# ETH-W5500.net
KiCad netlist of a schematic drawn in Altium Designer
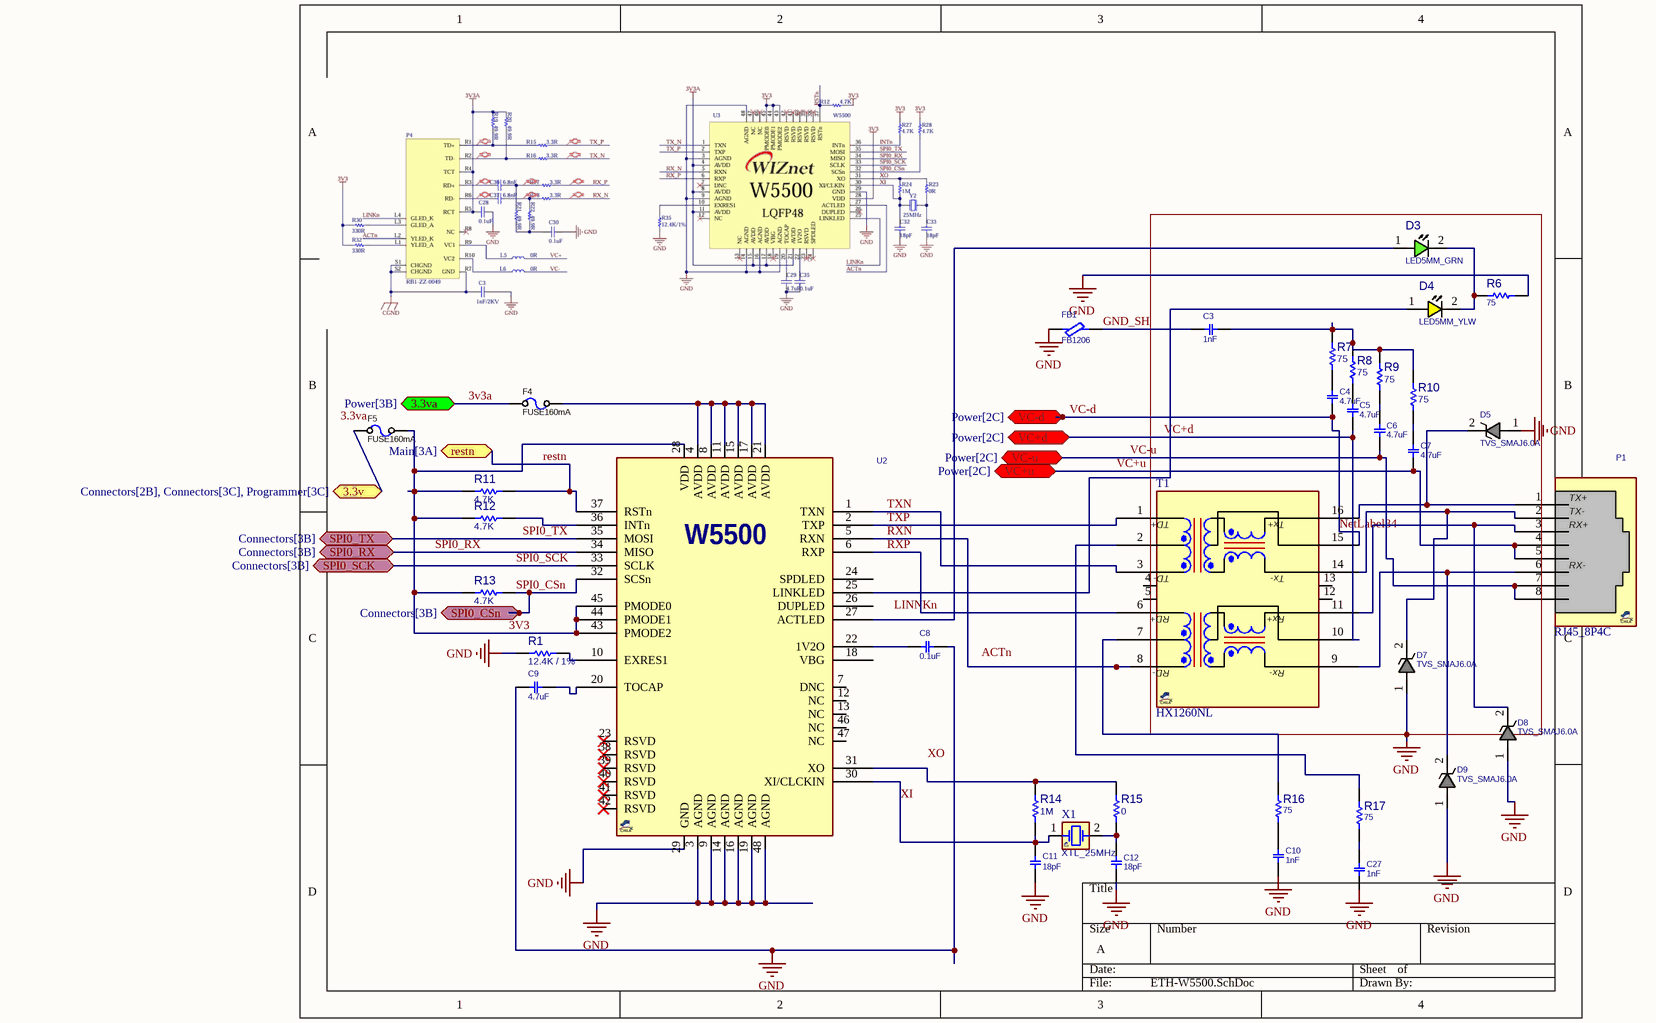
[diagram p0: ETH-W5500.SchDoc]

(export (version "E")
  (design (tool "Eeschema 10.0.6"))
  (components
    (comp (ref "C3")
      (value "1nF")
      (footprint "C_CERM_D3")
      (description "CAP, THD, CER MULTI LAYER,")
      (fields (field (name "MANF_P#") "MANF_PART#") (field (name "MANF") "MANF"))
      (libsource (lib "passive_thd") (part "CAP_THD_CER"))
    )
    (comp (ref "C4")
      (value "4.7uF")
      (footprint "C_CERM_D3")
      (description "CAP, THD, CER MULTI LAYER,")
      (fields (field (name "MANF_P#") "MANF_PART#") (field (name "MANF") "MANF"))
      (libsource (lib "passive_thd") (part "CAP_THD_CER"))
    )
    (comp (ref "C5")
      (value "4.7uF")
      (footprint "C_CERM_D3")
      (description "CAP, THD, CER MULTI LAYER,")
      (fields (field (name "MANF_P#") "MANF_PART#") (field (name "MANF") "MANF"))
      (libsource (lib "passive_thd") (part "CAP_THD_CER"))
    )
    (comp (ref "C6")
      (value "4.7uF")
      (footprint "C_CERM_D3")
      (description "CAP, THD, CER MULTI LAYER,")
      (fields (field (name "MANF_P#") "MANF_PART#") (field (name "MANF") "MANF"))
      (libsource (lib "passive_thd") (part "CAP_THD_CER"))
    )
    (comp (ref "C7")
      (value "4.7uF")
      (footprint "C_CERM_D3")
      (description "CAP, THD, CER MULTI LAYER,")
      (fields (field (name "MANF_P#") "MANF_PART#") (field (name "MANF") "MANF"))
      (libsource (lib "passive_thd") (part "CAP_THD_CER"))
    )
    (comp (ref "C8")
      (value "0.1uF")
      (footprint "C_CERM_D3")
      (description "CAP, THD, CER MULTI LAYER,")
      (fields (field (name "MANF_P#") "MANF_PART#") (field (name "MANF") "MANF"))
      (libsource (lib "passive_thd") (part "CAP_THD_CER"))
    )
    (comp (ref "C9")
      (value "4.7uF")
      (footprint "C_CERM_D3")
      (description "CAP, THD, CER MULTI LAYER,")
      (fields (field (name "MANF_P#") "MANF_PART#") (field (name "MANF") "MANF"))
      (libsource (lib "passive_thd") (part "CAP_THD_CER"))
    )
    (comp (ref "C10")
      (value "1nF")
      (footprint "C_CERM_D3")
      (description "CAP, THD, CER MULTI LAYER,")
      (fields (field (name "MANF_P#") "MANF_PART#") (field (name "MANF") "MANF"))
      (libsource (lib "passive_thd") (part "CAP_THD_CER"))
    )
    (comp (ref "C11")
      (value "18pF")
      (footprint "C_CERM_D3")
      (description "CAP, THD, CER MULTI LAYER,")
      (fields (field (name "MANF_P#") "MANF_PART#") (field (name "MANF") "MANF"))
      (libsource (lib "passive_thd") (part "CAP_THD_CER"))
    )
    (comp (ref "C12")
      (value "18pF")
      (footprint "C_CERM_D3")
      (description "CAP, THD, CER MULTI LAYER,")
      (fields (field (name "MANF_P#") "MANF_PART#") (field (name "MANF") "MANF"))
      (libsource (lib "passive_thd") (part "CAP_THD_CER"))
    )
    (comp (ref "C27")
      (value "1nF")
      (footprint "C_CERM_D3")
      (description "CAP, THD, CER MULTI LAYER,")
      (fields (field (name "MANF_P#") "MANF_PART#") (field (name "MANF") "MANF"))
      (libsource (lib "passive_thd") (part "CAP_THD_CER"))
    )
    (comp (ref "D3")
      (value "LED5MM_GRN")
      (footprint "LED5MM_GRN")
      (description "LED, THD, 5MM, GREEN")
      (fields (field (name "MANF") "MANF") (field (name "MANF_P#") "MANF_PART#"))
      (libsource (lib "led(diode)") (part "LED_THD_5MM_GRN"))
    )
    (comp (ref "D4")
      (value "LED5MM_YLW")
      (footprint "LED5MM_YLW")
      (description "LED, THD, 5MM, YELLOW")
      (fields (field (name "MANF") "MANF") (field (name "MANF_P#") "MANF_PART#"))
      (libsource (lib "led(diode)") (part "LED_THD_5MM_YLW"))
    )
    (comp (ref "D5")
      (value "TVS_SMAJ6.0A")
      (footprint "D_SMA")
      (description "TVS, ESD PROTECT")
      (fields (field (name "MANF_P#") "SMAJ6.0A"))
      (libsource (lib "protect_tvs_esd_fuse") (part "TVS_SMAJ6.0A"))
    )
    (comp (ref "D7")
      (value "TVS_SMAJ6.0A")
      (footprint "D_SMA")
      (description "TVS, ESD PROTECT")
      (fields (field (name "MANF_P#") "SMAJ6.0A"))
      (libsource (lib "protect_tvs_esd_fuse") (part "TVS_SMAJ6.0A"))
    )
    (comp (ref "D8")
      (value "TVS_SMAJ6.0A")
      (footprint "D_SMA")
      (description "TVS, ESD PROTECT")
      (fields (field (name "MANF_P#") "SMAJ6.0A"))
      (libsource (lib "protect_tvs_esd_fuse") (part "TVS_SMAJ6.0A"))
    )
    (comp (ref "D9")
      (value "TVS_SMAJ6.0A")
      (footprint "D_SMA")
      (description "TVS, ESD PROTECT")
      (fields (field (name "MANF_P#") "SMAJ6.0A"))
      (libsource (lib "protect_tvs_esd_fuse") (part "TVS_SMAJ6.0A"))
    )
    (comp (ref "F4")
      (value "FUSE160mA")
      (footprint "F1206")
      (description "Fuse, 160mA, 63VDC, 1206, SMD, Fast Acting")
      (fields (field (name "MANF") "Holly Fuse") (field (name "MANF_P#") "12T-0160L"))
      (libsource (lib "protect_tvs_esd_fuse") (part "FUSE_160mA_1206"))
    )
    (comp (ref "F5")
      (value "FUSE160mA")
      (footprint "F1206")
      (description "Fuse, 160mA, 63VDC, 1206, SMD, Fast Acting")
      (fields (field (name "MANF") "Holly Fuse") (field (name "MANF_P#") "12T-0160L"))
      (libsource (lib "protect_tvs_esd_fuse") (part "FUSE_160mA_1206"))
    )
    (comp (ref "FB1")
      (value "FB1206")
      (footprint "L1206")
      (description "FERRITE_Bead, 1206, 1.5A, 80mOhm, 600@100MHz")
      (fields (field (name "MANF") "Murata") (field (name "MANF_P#") "BLM31PG601SN1L"))
      (libsource (lib "emi_filter") (part "FBEAD_SMD_BLM31PG601"))
    )
    (comp (ref "P1")
      (value "RJ45_8P4C")
      (footprint "RJ45_8_RA_TD")
      (description "RJ45, 8P4C, RightAngle, Tab Down")
      (fields (field (name "MANF") "WURTH") (field (name "MANF_P#") "615008137121, 615008143721"))
      (libsource (lib "conn_rj_ModularJack") (part "RJ45_8P4C_RATD"))
    )
    (comp (ref "R1")
      (value "12.4K / 1%")
      (footprint "R0603")
      (description "RESISTOR, SMD")
      (libsource (lib "passive_smd") (part "RES_SMD"))
    )
    (comp (ref "R6")
      (value "75")
      (footprint "R025W_AX04")
      (description "RESISTOR, THD")
      (fields (field (name "MANF_P#") "RK73H1ETTP4701F") (field (name "MANF") "KOA SPEER"))
      (libsource (lib "passive_thd") (part "RES_THD"))
    )
    (comp (ref "R7")
      (value "75")
      (footprint "R0402")
      (description "RESISTOR, SMD")
      (libsource (lib "passive_smd") (part "RES_SMD"))
    )
    (comp (ref "R8")
      (value "75")
      (footprint "R0402")
      (description "RESISTOR, SMD")
      (libsource (lib "passive_smd") (part "RES_SMD"))
    )
    (comp (ref "R9")
      (value "75")
      (footprint "R0402")
      (description "RESISTOR, SMD")
      (libsource (lib "passive_smd") (part "RES_SMD"))
    )
    (comp (ref "R10")
      (value "75")
      (footprint "R0402")
      (description "RESISTOR, SMD")
      (libsource (lib "passive_smd") (part "RES_SMD"))
    )
    (comp (ref "R11")
      (value "4.7K")
      (footprint "R1206")
      (description "RESISTOR, SMD")
      (libsource (lib "passive_smd") (part "RES_SMD_1206"))
    )
    (comp (ref "R12")
      (value "4.7K")
      (footprint "R1206")
      (description "RESISTOR, SMD")
      (libsource (lib "passive_smd") (part "RES_SMD_1206"))
    )
    (comp (ref "R13")
      (value "4.7K")
      (footprint "R1206")
      (description "RESISTOR, SMD")
      (libsource (lib "passive_smd") (part "RES_SMD_1206"))
    )
    (comp (ref "R14")
      (value "1M")
      (footprint "R0603")
      (description "RESISTOR, SMD")
      (libsource (lib "passive_smd") (part "RES_SMD_0603"))
    )
    (comp (ref "R15")
      (value "0")
      (footprint "R0603")
      (description "RESISTOR, SMD")
      (libsource (lib "passive_smd") (part "RES_SMD_0603"))
    )
    (comp (ref "R16")
      (value "75")
      (footprint "R025W_AX04")
      (description "RESISTOR, THD")
      (fields (field (name "MANF_P#") "RK73H1ETTP4701F") (field (name "MANF") "KOA SPEER"))
      (libsource (lib "passive_thd") (part "RES_THD"))
    )
    (comp (ref "R17")
      (value "75")
      (footprint "R025W_AX04")
      (description "RESISTOR, THD")
      (fields (field (name "MANF_P#") "RK73H1ETTP4701F") (field (name "MANF") "KOA SPEER"))
      (libsource (lib "passive_thd") (part "RES_THD"))
    )
    (comp (ref "T1")
      (value "HX1260NL")
      (footprint "SO_16_7W6H")
      (description "Transformer, LAN, 100 Base-T , 1CT:1CT, 350uH")
      (fields (field (name "MANF") "Pulse"))
      (libsource (lib "transformer_ethernet") (part "HX1260NL_SO16"))
    )
    (comp (ref "U2")
      (value "~")
      (footprint "QFG50_48")
      (description "Ethernet Controller, 10/100, SPI, DMA")
      (fields (field (name "MANF") "WIZNET") (field (name "MANF_P#") "W5500"))
      (libsource (lib "ethernet") (part "W5500_QFP48"))
    )
    (comp (ref "X1")
      (value "XTL_25MHz")
      (footprint "XTL_2_5032")
      (description "Crystal 2 5X3.2mm")
      (fields (field (name "MANF") "ABRACON") (field (name "MANF_P#") "ABM3-25.000MHZ-B2-T"))
      (libsource (lib "crystal") (part "XTL_2_25MHz"))
    )
  )
  (nets
    (net (code "1") (name "/3.3v") (class "Default")
      (node (ref "F5") (pin "1") (pinfunction "1_1") (pintype "passive"))
    )
    (net (code "2") (name "/3.3va") (class "Default")
      (node (ref "F4") (pin "1") (pinfunction "1_1") (pintype "passive"))
    )
    (net (code "3") (name "/3V3") (class "Default")
      (node (ref "F5") (pin "2") (pinfunction "2_2") (pintype "passive"))
      (node (ref "R11") (pin "1") (pinfunction "1_1") (pintype "passive"))
      (node (ref "R12") (pin "1") (pinfunction "1_1") (pintype "passive"))
      (node (ref "R13") (pin "1") (pinfunction "1_1") (pintype "passive"))
      (node (ref "U2") (pin "28") (pinfunction "VDD_28") (pintype "passive"))
      (node (ref "U2") (pin "43") (pinfunction "PMODE2_43") (pintype "passive"))
      (node (ref "U2") (pin "44") (pinfunction "PMODE1_44") (pintype "passive"))
      (node (ref "U2") (pin "45") (pinfunction "PMODE0_45") (pintype "passive"))
    )
    (net (code "5") (name "/GND_SH") (class "Default")
      (node (ref "C3") (pin "2") (pinfunction "2_2") (pintype "passive"))
      (node (ref "FB1") (pin "2") (pinfunction "2_2") (pintype "passive"))
    )
    (net (code "7") (name "/NetLabel34") (class "Default")
      (node (ref "C4") (pin "1") (pinfunction "1_1") (pintype "passive"))
      (node (ref "T1") (pin "15") (pinfunction "CTX_15") (pintype "passive"))
    )
    (net (code "8") (name "/RXN") (class "Default")
      (node (ref "T1") (pin "8") (pinfunction "RD-_8") (pintype "passive"))
      (node (ref "U2") (pin "5") (pinfunction "RXN_5") (pintype "passive"))
    )
    (net (code "9") (name "/RXP") (class "Default")
      (node (ref "T1") (pin "6") (pinfunction "RD+_6") (pintype "passive"))
      (node (ref "U2") (pin "6") (pinfunction "RXP_6") (pintype "passive"))
    )
    (net (code "10") (name "/SPI0_CSn") (class "Default")
      (node (ref "R13") (pin "2") (pinfunction "2_2") (pintype "passive"))
      (node (ref "U2") (pin "32") (pinfunction "SCSn_32") (pintype "passive"))
    )
    (net (code "11") (name "/SPI0_RX") (class "Default")
      (node (ref "U2") (pin "34") (pinfunction "MISO_34") (pintype "passive"))
    )
    (net (code "12") (name "/SPI0_SCK") (class "Default")
      (node (ref "U2") (pin "33") (pinfunction "SCLK_33") (pintype "passive"))
    )
    (net (code "13") (name "/SPI0_TX") (class "Default")
      (node (ref "U2") (pin "35") (pinfunction "MOSI_35") (pintype "passive"))
    )
    (net (code "14") (name "/TXN") (class "Default")
      (node (ref "T1") (pin "3") (pinfunction "TD-_3") (pintype "passive"))
      (node (ref "U2") (pin "1") (pinfunction "TXN_1") (pintype "passive"))
    )
    (net (code "15") (name "/TXP") (class "Default")
      (node (ref "T1") (pin "1") (pinfunction "TD+_1") (pintype "passive"))
      (node (ref "U2") (pin "2") (pinfunction "TXP_2") (pintype "passive"))
    )
    (net (code "16") (name "/VC+d") (class "Default")
      (node (ref "C5") (pin "1") (pinfunction "1_1") (pintype "passive"))
      (node (ref "T1") (pin "10") (pinfunction "CRX_10") (pintype "passive"))
    )
    (net (code "17") (name "/VC+u") (class "Default")
      (node (ref "C7") (pin "1") (pinfunction "1_1") (pintype "passive"))
      (node (ref "P1") (pin "4") (pinfunction "NC_4") (pintype "passive"))
      (node (ref "P1") (pin "5") (pinfunction "NC_5") (pintype "passive"))
    )
    (net (code "18") (name "/VC-u") (class "Default")
      (node (ref "C6") (pin "1") (pinfunction "1_1") (pintype "passive"))
      (node (ref "P1") (pin "7") (pinfunction "NC_7") (pintype "passive"))
      (node (ref "P1") (pin "8") (pinfunction "NC_8") (pintype "passive"))
    )
    (net (code "19") (name "/XI") (class "Default")
      (node (ref "C11") (pin "2") (pinfunction "2_2") (pintype "passive"))
      (node (ref "R14") (pin "1") (pinfunction "1_1") (pintype "passive"))
      (node (ref "U2") (pin "30") (pinfunction "XI/CLCKIN_30") (pintype "passive"))
      (node (ref "X1") (pin "1") (pinfunction "OSC1_1") (pintype "passive"))
    )
    (net (code "21") (name "/restn") (class "Default")
      (node (ref "R11") (pin "2") (pinfunction "2_2") (pintype "passive"))
      (node (ref "U2") (pin "37") (pinfunction "RSTn_37") (pintype "passive"))
    )
    (net (code "22") (name "GND") (class "Default")
      (node (ref "C10") (pin "1") (pinfunction "1_1") (pintype "passive"))
      (node (ref "C11") (pin "1") (pinfunction "1_1") (pintype "passive"))
      (node (ref "C12") (pin "1") (pinfunction "1_1") (pintype "passive"))
      (node (ref "C27") (pin "1") (pinfunction "1_1") (pintype "passive"))
      (node (ref "C8") (pin "2") (pinfunction "2_2") (pintype "passive"))
      (node (ref "C9") (pin "1") (pinfunction "1_1") (pintype "passive"))
      (node (ref "D5") (pin "1") (pinfunction "1_1") (pintype "passive"))
      (node (ref "D7") (pin "1") (pinfunction "1_1") (pintype "passive"))
      (node (ref "D8") (pin "1") (pinfunction "1_1") (pintype "passive"))
      (node (ref "D9") (pin "1") (pinfunction "1_1") (pintype "passive"))
      (node (ref "FB1") (pin "1") (pinfunction "1_1") (pintype "passive"))
      (node (ref "R1") (pin "1") (pinfunction "1_1") (pintype "passive"))
      (node (ref "R6") (pin "2") (pinfunction "2_2") (pintype "passive"))
      (node (ref "U2") (pin "14") (pinfunction "AGND_14") (pintype "passive"))
      (node (ref "U2") (pin "16") (pinfunction "AGND_16") (pintype "passive"))
      (node (ref "U2") (pin "19") (pinfunction "AGND_19") (pintype "passive"))
      (node (ref "U2") (pin "29") (pinfunction "GND_29") (pintype "passive"))
      (node (ref "U2") (pin "3") (pinfunction "AGND_3") (pintype "passive"))
      (node (ref "U2") (pin "48") (pinfunction "AGND_48") (pintype "passive"))
      (node (ref "U2") (pin "9") (pinfunction "AGND_9") (pintype "passive"))
    )
    (net (code "23") (name "Net-(C3-Pad1)") (class "Default")
      (node (ref "C3") (pin "1") (pinfunction "1_1") (pintype "passive"))
      (node (ref "R10") (pin "2") (pinfunction "2_2") (pintype "passive"))
      (node (ref "R7") (pin "2") (pinfunction "2_2") (pintype "passive"))
      (node (ref "R8") (pin "2") (pinfunction "2_2") (pintype "passive"))
      (node (ref "R9") (pin "2") (pinfunction "2_2") (pintype "passive"))
    )
    (net (code "24") (name "Net-(C4-Pad2)") (class "Default")
      (node (ref "C4") (pin "2") (pinfunction "2_2") (pintype "passive"))
      (node (ref "R7") (pin "1") (pinfunction "1_1") (pintype "passive"))
    )
    (net (code "25") (name "Net-(C5-Pad2)") (class "Default")
      (node (ref "C5") (pin "2") (pinfunction "2_2") (pintype "passive"))
      (node (ref "R8") (pin "1") (pinfunction "1_1") (pintype "passive"))
    )
    (net (code "26") (name "Net-(C6-Pad2)") (class "Default")
      (node (ref "C6") (pin "2") (pinfunction "2_2") (pintype "passive"))
      (node (ref "R9") (pin "1") (pinfunction "1_1") (pintype "passive"))
    )
    (net (code "27") (name "Net-(C7-Pad2)") (class "Default")
      (node (ref "C7") (pin "2") (pinfunction "2_2") (pintype "passive"))
      (node (ref "R10") (pin "1") (pinfunction "1_1") (pintype "passive"))
    )
    (net (code "28") (name "Net-(C10-Pad2)") (class "Default")
      (node (ref "C10") (pin "2") (pinfunction "2_2") (pintype "passive"))
      (node (ref "R16") (pin "2") (pinfunction "2_2") (pintype "passive"))
    )
    (net (code "29") (name "Net-(C27-Pad2)") (class "Default")
      (node (ref "C27") (pin "2") (pinfunction "2_2") (pintype "passive"))
      (node (ref "R17") (pin "2") (pinfunction "2_2") (pintype "passive"))
    )
    (net (code "30") (name "Net-(D3-ANODE)") (class "Default")
      (node (ref "D3") (pin "1") (pinfunction "ANODE_1") (pintype "passive"))
      (node (ref "U2") (pin "27") (pinfunction "ACTLED_27") (pintype "passive"))
    )
    (net (code "31") (name "Net-(D3-CATHODE)") (class "Default")
      (node (ref "D3") (pin "2") (pinfunction "CATHODE_2") (pintype "passive"))
      (node (ref "D4") (pin "2") (pinfunction "CATHODE_2") (pintype "passive"))
      (node (ref "R6") (pin "1") (pinfunction "1_1") (pintype "passive"))
    )
    (net (code "32") (name "Net-(D4-ANODE)") (class "Default")
      (node (ref "D4") (pin "1") (pinfunction "ANODE_1") (pintype "passive"))
      (node (ref "U2") (pin "25") (pinfunction "LINKLED_25") (pintype "passive"))
    )
    (net (code "33") (name "Net-(F4-Pad2)") (class "Default")
      (node (ref "F4") (pin "2") (pinfunction "2_2") (pintype "passive"))
      (node (ref "U2") (pin "11") (pinfunction "AVDD_11") (pintype "passive"))
      (node (ref "U2") (pin "15") (pinfunction "AVDD_15") (pintype "passive"))
      (node (ref "U2") (pin "17") (pinfunction "AVDD_17") (pintype "passive"))
      (node (ref "U2") (pin "21") (pinfunction "AVDD_21") (pintype "passive"))
      (node (ref "U2") (pin "4") (pinfunction "AVDD_4") (pintype "passive"))
      (node (ref "U2") (pin "8") (pinfunction "AVDD_8") (pintype "passive"))
    )
    (net (code "34") (name "Net-(P1-RX+)") (class "Default")
      (node (ref "D8") (pin "2") (pinfunction "2_2") (pintype "passive"))
      (node (ref "P1") (pin "3") (pinfunction "RX+_3") (pintype "passive"))
      (node (ref "T1") (pin "11") (pinfunction "RX+_11") (pintype "passive"))
    )
    (net (code "35") (name "Net-(P1-RX-)") (class "Default")
      (node (ref "D9") (pin "2") (pinfunction "2_2") (pintype "passive"))
      (node (ref "P1") (pin "6") (pinfunction "RX-_6") (pintype "passive"))
      (node (ref "T1") (pin "9") (pinfunction "RX-_9") (pintype "passive"))
    )
    (net (code "36") (name "Net-(P1-TX+)") (class "Default")
      (node (ref "D5") (pin "2") (pinfunction "2_2") (pintype "passive"))
      (node (ref "P1") (pin "1") (pinfunction "TX+_1") (pintype "passive"))
      (node (ref "T1") (pin "16") (pinfunction "TX+_16") (pintype "passive"))
    )
    (net (code "37") (name "Net-(P1-TX-)") (class "Default")
      (node (ref "D7") (pin "2") (pinfunction "2_2") (pintype "passive"))
      (node (ref "P1") (pin "2") (pinfunction "TX-_2") (pintype "passive"))
      (node (ref "T1") (pin "14") (pinfunction "TX-_14") (pintype "passive"))
    )
    (net (code "38") (name "Net-(T1-CRD)") (class "Default")
      (node (ref "R16") (pin "1") (pinfunction "1_1") (pintype "passive"))
      (node (ref "T1") (pin "7") (pinfunction "CRD_7") (pintype "passive"))
    )
    (net (code "39") (name "Net-(T1-CTD)") (class "Default")
      (node (ref "R17") (pin "1") (pinfunction "1_1") (pintype "passive"))
      (node (ref "T1") (pin "2") (pinfunction "CTD_2") (pintype "passive"))
    )
    (net (code "40") (name "Net-(U2-1V2O)") (class "Default")
      (node (ref "C8") (pin "1") (pinfunction "1_1") (pintype "passive"))
      (node (ref "U2") (pin "22") (pinfunction "1V2O_22") (pintype "passive"))
    )
    (net (code "41") (name "Net-(U2-EXRES1)") (class "Default")
      (node (ref "R1") (pin "2") (pinfunction "2_2") (pintype "passive"))
      (node (ref "U2") (pin "10") (pinfunction "EXRES1_10") (pintype "passive"))
    )
    (net (code "42") (name "Net-(U2-INTn)") (class "Default")
      (node (ref "R12") (pin "2") (pinfunction "2_2") (pintype "passive"))
      (node (ref "U2") (pin "36") (pinfunction "INTn_36") (pintype "passive"))
    )
    (net (code "43") (name "Net-(U2-TOCAP)") (class "Default")
      (node (ref "C9") (pin "2") (pinfunction "2_2") (pintype "passive"))
      (node (ref "U2") (pin "20") (pinfunction "TOCAP_20") (pintype "passive"))
    )
    (net (code "44") (name "Net-(U2-XO)") (class "Default")
      (node (ref "R14") (pin "2") (pinfunction "2_2") (pintype "passive"))
      (node (ref "R15") (pin "2") (pinfunction "2_2") (pintype "passive"))
      (node (ref "U2") (pin "31") (pinfunction "XO_31") (pintype "passive"))
    )
    (net (code "45") (name "Net-(X1-OSC2)") (class "Default")
      (node (ref "C12") (pin "2") (pinfunction "2_2") (pintype "passive"))
      (node (ref "R15") (pin "1") (pinfunction "1_1") (pintype "passive"))
      (node (ref "X1") (pin "2") (pinfunction "OSC2_2") (pintype "passive"))
    )
    (net (code "46") (name "unconnected-(T1-NC_1-Pad4)") (class "Default")
      (node (ref "T1") (pin "4") (pinfunction "NC_1_4") (pintype "passive"))
    )
    (net (code "47") (name "unconnected-(T1-NC_2-Pad5)") (class "Default")
      (node (ref "T1") (pin "5") (pinfunction "NC_2_5") (pintype "passive"))
    )
    (net (code "48") (name "unconnected-(T1-NC_3-Pad12)") (class "Default")
      (node (ref "T1") (pin "12") (pinfunction "NC_3_12") (pintype "passive"))
    )
    (net (code "49") (name "unconnected-(T1-NC_4-Pad13)") (class "Default")
      (node (ref "T1") (pin "13") (pinfunction "NC_4_13") (pintype "passive"))
    )
    (net (code "50") (name "unconnected-(U2-DNC-Pad7)") (class "Default")
      (node (ref "U2") (pin "7") (pinfunction "DNC_7") (pintype "passive"))
    )
    (net (code "51") (name "unconnected-(U2-DUPLED-Pad26)") (class "Default")
      (node (ref "U2") (pin "26") (pinfunction "DUPLED_26") (pintype "passive"))
    )
    (net (code "52") (name "unconnected-(U2-NC-Pad12)") (class "Default")
      (node (ref "U2") (pin "12") (pinfunction "NC_12") (pintype "passive"))
    )
    (net (code "53") (name "unconnected-(U2-NC-Pad13)") (class "Default")
      (node (ref "U2") (pin "13") (pinfunction "NC_13") (pintype "passive"))
    )
    (net (code "54") (name "unconnected-(U2-NC-Pad46)") (class "Default")
      (node (ref "U2") (pin "46") (pinfunction "NC_46") (pintype "passive"))
    )
    (net (code "55") (name "unconnected-(U2-NC-Pad47)") (class "Default")
      (node (ref "U2") (pin "47") (pinfunction "NC_47") (pintype "passive"))
    )
    (net (code "56") (name "unconnected-(U2-RSVD-Pad23)") (class "Default")
      (node (ref "U2") (pin "23") (pinfunction "RSVD_23") (pintype "passive+no_connect"))
    )
    (net (code "57") (name "unconnected-(U2-RSVD-Pad38)") (class "Default")
      (node (ref "U2") (pin "38") (pinfunction "RSVD_38") (pintype "passive+no_connect"))
    )
    (net (code "58") (name "unconnected-(U2-RSVD-Pad39)") (class "Default")
      (node (ref "U2") (pin "39") (pinfunction "RSVD_39") (pintype "passive+no_connect"))
    )
    (net (code "59") (name "unconnected-(U2-RSVD-Pad40)") (class "Default")
      (node (ref "U2") (pin "40") (pinfunction "RSVD_40") (pintype "passive+no_connect"))
    )
    (net (code "60") (name "unconnected-(U2-RSVD-Pad41)") (class "Default")
      (node (ref "U2") (pin "41") (pinfunction "RSVD_41") (pintype "passive+no_connect"))
    )
    (net (code "61") (name "unconnected-(U2-RSVD-Pad42)") (class "Default")
      (node (ref "U2") (pin "42") (pinfunction "RSVD_42") (pintype "passive+no_connect"))
    )
    (net (code "62") (name "unconnected-(U2-SPDLED-Pad24)") (class "Default")
      (node (ref "U2") (pin "24") (pinfunction "SPDLED_24") (pintype "passive"))
    )
    (net (code "63") (name "unconnected-(U2-VBG-Pad18)") (class "Default")
      (node (ref "U2") (pin "18") (pinfunction "VBG_18") (pintype "passive"))
    )
  )
)
